# untitled.net
KiCad netlist of a schematic drawn in EAGLE
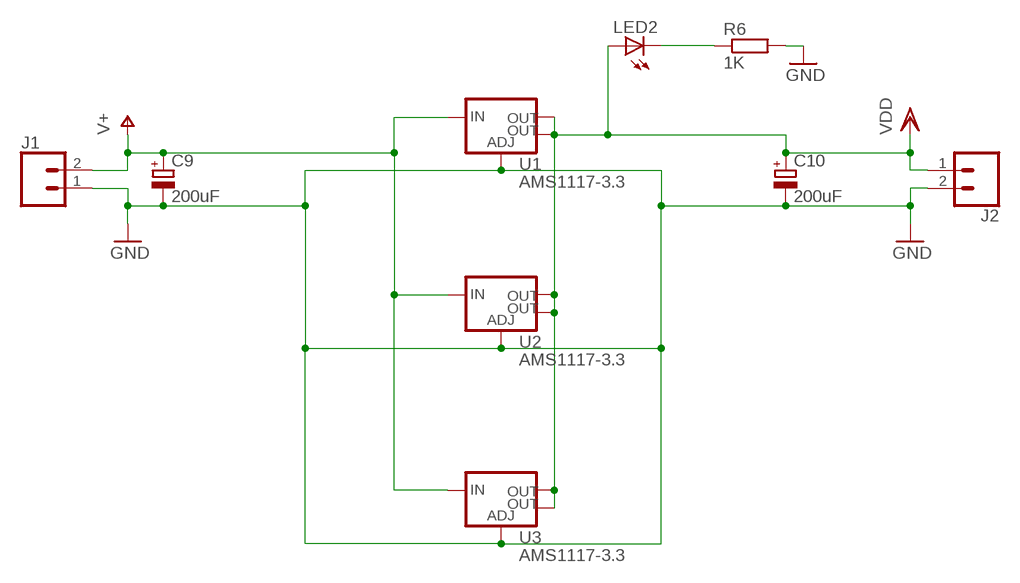
[diagram p0: schematic, sheet 1]

(export (version "E")
  (design (tool "Eeschema 10.0.6"))
  (components
    (comp (ref "C9")
      (value "200uF")
      (footprint "eagle-import:153CLV-0810")
      (libsource (lib "eagle-import") (part "CPOL-EU153CLV-0810"))
    )
    (comp (ref "C10")
      (value "200uF")
      (footprint "eagle-import:153CLV-0810")
      (libsource (lib "eagle-import") (part "CPOL-EU153CLV-0810"))
    )
    (comp (ref "J1")
      (value "CONN_025MM")
      (footprint "eagle-import:SCREWTERMINAL-5MM-2")
      (libsource (lib "eagle-import") (part "CONN_025MM"))
    )
    (comp (ref "J2")
      (value "CONN_025MM")
      (footprint "eagle-import:SCREWTERMINAL-5MM-2")
      (libsource (lib "eagle-import") (part "CONN_025MM"))
    )
    (comp (ref "LED2")
      (value "LED5MM")
      (footprint "eagle-import:LED5MM")
      (libsource (lib "eagle-import") (part "LED5MM"))
    )
    (comp (ref "R6")
      (value "1K")
      (footprint "eagle-import:R0805")
      (libsource (lib "eagle-import") (part "R-EU_R0805"))
    )
    (comp (ref "U1")
      (value "AMS1117-3.3")
      (footprint "eagle-import:SOT223")
      (libsource (lib "eagle-import") (part "V_REG_LM1117SOT223"))
    )
    (comp (ref "U2")
      (value "AMS1117-3.3")
      (footprint "eagle-import:SOT223")
      (libsource (lib "eagle-import") (part "V_REG_LM1117SOT223"))
    )
    (comp (ref "U3")
      (value "AMS1117-3.3")
      (footprint "eagle-import:SOT223")
      (libsource (lib "eagle-import") (part "V_REG_LM1117SOT223"))
    )
  )
  (nets
    (net (code "1") (name "GND") (class "Default")
      (node (ref "C10") (pin "-") (pinfunction "-_-") (pintype "passive"))
      (node (ref "C9") (pin "-") (pinfunction "-_-") (pintype "passive"))
      (node (ref "J1") (pin "1") (pinfunction "1_1") (pintype "passive"))
      (node (ref "J2") (pin "2") (pinfunction "2_2") (pintype "passive"))
      (node (ref "R6") (pin "2") (pinfunction "2_2") (pintype "passive"))
      (node (ref "U1") (pin "1") (pinfunction "ADJ_1") (pintype "input"))
      (node (ref "U2") (pin "1") (pinfunction "ADJ_1") (pintype "input"))
      (node (ref "U3") (pin "1") (pinfunction "ADJ_1") (pintype "input"))
    )
    (net (code "2") (name "Net-(LED2-C)") (class "Default")
      (node (ref "LED2") (pin "K") (pinfunction "C_K") (pintype "passive"))
      (node (ref "R6") (pin "1") (pinfunction "1_1") (pintype "passive"))
    )
    (net (code "3") (name "V+") (class "Default")
      (node (ref "C9") (pin "+") (pinfunction "+_+") (pintype "passive"))
      (node (ref "J1") (pin "2") (pinfunction "2_2") (pintype "passive"))
      (node (ref "U1") (pin "3") (pinfunction "IN_3") (pintype "input"))
      (node (ref "U2") (pin "3") (pinfunction "IN_3") (pintype "input"))
      (node (ref "U3") (pin "3") (pinfunction "IN_3") (pintype "input"))
    )
    (net (code "4") (name "VDD") (class "Default")
      (node (ref "C10") (pin "+") (pinfunction "+_+") (pintype "passive"))
      (node (ref "J2") (pin "1") (pinfunction "1_1") (pintype "passive"))
      (node (ref "LED2") (pin "A") (pinfunction "A_A") (pintype "passive"))
      (node (ref "U1") (pin "2") (pinfunction "OUT_2") (pintype "output"))
      (node (ref "U1") (pin "4") (pinfunction "OUT_4") (pintype "output"))
      (node (ref "U2") (pin "2") (pinfunction "OUT_2") (pintype "output"))
      (node (ref "U2") (pin "4") (pinfunction "OUT_4") (pintype "output"))
      (node (ref "U3") (pin "2") (pinfunction "OUT_2") (pintype "output"))
      (node (ref "U3") (pin "4") (pinfunction "OUT_4") (pintype "output"))
    )
  )
)
